# super.net
KiCad netlist of a schematic drawn in Altium Designer
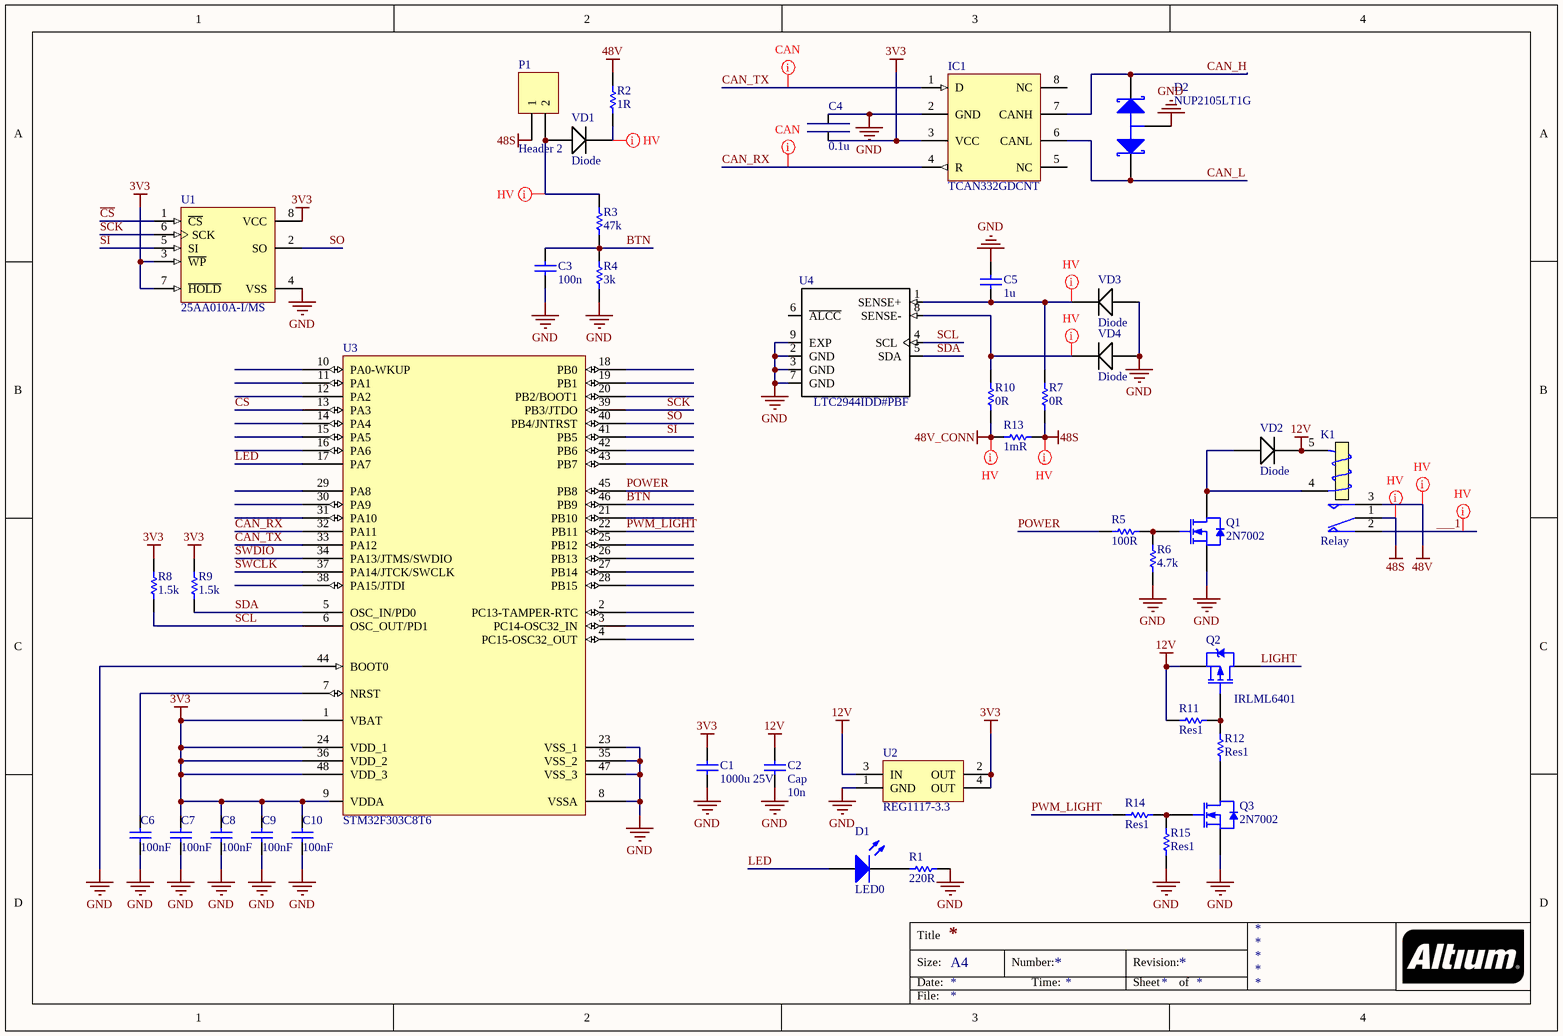
[diagram p0: super.SchDoc]

(export (version "E")
  (design (tool "Eeschema 10.0.6"))
  (components
    (comp (ref "C1")
      (value "1000u 25V")
      (footprint "RR_B")
      (description "Capacitor")
      (fields (field (name "PUBLISHER") "Altium Limited"))
      (libsource (lib "Miscellaneous Devices") (part "Cap"))
    )
    (comp (ref "C2")
      (value "Cap")
      (footprint "0603x")
      (description "Capacitor")
      (fields (field (name "ALTIUM_VALUE") "10n") (field (name "PUBLISHER") "Altium Limited"))
      (libsource (lib "Miscellaneous Devices") (part "Cap"))
    )
    (comp (ref "C3")
      (value "100n")
      (footprint "0603x")
      (description "Capacitor")
      (fields (field (name "PUBLISHER") "Altium Limited"))
      (libsource (lib "Miscellaneous Devices") (part "Cap"))
    )
    (comp (ref "C4")
      (value "0.1u")
      (footprint "Condensator:CAPC1608X08N(0603)")
      (libsource (lib "Condensator") (part "Ceramic Chip Capacitor"))
    )
    (comp (ref "C5")
      (value "1u")
      (footprint "0603x")
      (description "Capacitor")
      (fields (field (name "PUBLISHER") "Altium Limited"))
      (libsource (lib "Miscellaneous Devices") (part "Cap"))
    )
    (comp (ref "C6")
      (value "100nF")
      (footprint "0603x")
      (description "Capacitor")
      (fields (field (name "Comment") "Cap") (field (name "PUBLISHER") "Altium Limited"))
      (libsource (lib "Miscellaneous Devices") (part "Cap"))
    )
    (comp (ref "C7")
      (value "100nF")
      (footprint "0603x")
      (description "Capacitor")
      (fields (field (name "Comment") "Cap") (field (name "PUBLISHER") "Altium Limited"))
      (libsource (lib "Miscellaneous Devices") (part "Cap"))
    )
    (comp (ref "C8")
      (value "100nF")
      (footprint "0603x")
      (description "Capacitor")
      (fields (field (name "Comment") "Cap") (field (name "PUBLISHER") "Altium Limited"))
      (libsource (lib "Miscellaneous Devices") (part "Cap"))
    )
    (comp (ref "C9")
      (value "100nF")
      (footprint "0603x")
      (description "Capacitor")
      (fields (field (name "Comment") "Cap") (field (name "PUBLISHER") "Altium Limited"))
      (libsource (lib "Miscellaneous Devices") (part "Cap"))
    )
    (comp (ref "C10")
      (value "100nF")
      (footprint "0603x")
      (description "Capacitor")
      (fields (field (name "Comment") "Cap") (field (name "PUBLISHER") "Altium Limited"))
      (libsource (lib "Miscellaneous Devices") (part "Cap"))
    )
    (comp (ref "D1")
      (value "LED0")
      (footprint "HDR1X2")
      (description "Typical INFRARED GaAs LED")
      (fields (field (name "PUBLISHER") "Altium Limited"))
      (libsource (lib "Miscellaneous Devices") (part "LED0"))
    )
    (comp (ref "D2")
      (value "NUP2105LT1G")
      (footprint "SOT-23_M")
      (description "Schottky Barrier Double Diode")
      (libsource (lib "Philips Discrete Diode - Schottky") (part "BAT54A"))
    )
    (comp (ref "IC1")
      (value "TCAN332GDCNT")
      (footprint "SOT23-8_L")
      (libsource (lib "CustomLib") (part "TCAN332GDCNT"))
    )
    (comp (ref "K1")
      (value "Relay")
      (footprint "RELAY_12V_MICRO")
      (description "SPDT Relay")
      (fields (field (name "PUBLISHER") "Altium Limited"))
      (libsource (lib "Miscellaneous Devices") (part "Relay"))
    )
    (comp (ref "P1")
      (value "Header 2")
      (footprint "HDR1X2")
      (description "Header, 2-Pin")
      (fields (field (name "PUBLISHER") "Altium Limited"))
      (libsource (lib "Miscellaneous Connectors") (part "Header 2"))
    )
    (comp (ref "Q1")
      (value "2N7002")
      (footprint "SOT23_N")
      (description "N-channel Enhancement Mode Field-effect Transistor")
      (fields (field (name "PUBLISHER") "Altium Limited"))
      (libsource (lib "Philips Discrete MOSFET - Low Power") (part "2N7002"))
    )
    (comp (ref "Q2")
      (value "IRLML6401")
      (footprint "Micro3_N")
      (description "HEXFET Power MOSFET")
      (fields (field (name "PUBLISHER") "Altium Limited"))
      (libsource (lib "IR Discrete MOSFET - Power") (part "IRLML6401"))
    )
    (comp (ref "Q3")
      (value "2N7002")
      (footprint "SOT23_N")
      (description "N-channel Enhancement Mode Field-effect Transistor")
      (fields (field (name "PUBLISHER") "Altium Limited"))
      (libsource (lib "Philips Discrete MOSFET - Low Power") (part "2N7002"))
    )
    (comp (ref "R1")
      (value "220R")
      (footprint "0603x")
      (description "Resistor")
      (fields (field (name "PUBLISHER") "Altium Limited"))
      (libsource (lib "Miscellaneous Devices") (part "Res1"))
    )
    (comp (ref "R2")
      (value "1R")
      (footprint "2512")
      (description "Resistor")
      (fields (field (name "PUBLISHER") "Altium Limited"))
      (libsource (lib "Miscellaneous Devices") (part "Res1"))
    )
    (comp (ref "R3")
      (value "47k")
      (footprint "0603x")
      (description "Resistor")
      (fields (field (name "PUBLISHER") "Altium Limited"))
      (libsource (lib "Miscellaneous Devices") (part "Res1"))
    )
    (comp (ref "R4")
      (value "3k")
      (footprint "0603x")
      (description "Resistor")
      (fields (field (name "PUBLISHER") "Altium Limited"))
      (libsource (lib "Miscellaneous Devices") (part "Res1"))
    )
    (comp (ref "R5")
      (value "100R")
      (footprint "0603x")
      (description "Resistor")
      (fields (field (name "PUBLISHER") "Altium Limited"))
      (libsource (lib "Miscellaneous Devices") (part "Res1"))
    )
    (comp (ref "R6")
      (value "4.7k")
      (footprint "0603x")
      (description "Resistor")
      (fields (field (name "PUBLISHER") "Altium Limited"))
      (libsource (lib "Miscellaneous Devices") (part "Res1"))
    )
    (comp (ref "R7")
      (value "0R")
      (footprint "0603x")
      (description "Resistor")
      (fields (field (name "PUBLISHER") "Altium Limited"))
      (libsource (lib "Miscellaneous Devices") (part "Res1"))
    )
    (comp (ref "R8")
      (value "1.5k")
      (footprint "0603x")
      (description "Resistor")
      (fields (field (name "PUBLISHER") "Altium Limited"))
      (libsource (lib "Miscellaneous Devices") (part "Res1"))
    )
    (comp (ref "R9")
      (value "1.5k")
      (footprint "0603x")
      (description "Resistor")
      (fields (field (name "PUBLISHER") "Altium Limited"))
      (libsource (lib "Miscellaneous Devices") (part "Res1"))
    )
    (comp (ref "R10")
      (value "0R")
      (footprint "0603x")
      (description "Resistor")
      (fields (field (name "PUBLISHER") "Altium Limited"))
      (libsource (lib "Miscellaneous Devices") (part "Res1"))
    )
    (comp (ref "R11")
      (value "Res1")
      (footprint "0603x")
      (description "Resistor")
      (fields (field (name "PUBLISHER") "Altium Limited"))
      (libsource (lib "Miscellaneous Devices") (part "Res1"))
    )
    (comp (ref "R12")
      (value "Res1")
      (footprint "0603x")
      (description "Resistor")
      (fields (field (name "PUBLISHER") "Altium Limited"))
      (libsource (lib "Miscellaneous Devices") (part "Res1"))
    )
    (comp (ref "R13")
      (value "1mR")
      (footprint "2512")
      (description "Resistor")
      (fields (field (name "PUBLISHER") "Altium Limited"))
      (libsource (lib "Miscellaneous Devices") (part "Res1"))
    )
    (comp (ref "R14")
      (value "Res1")
      (footprint "0603x")
      (description "Resistor")
      (fields (field (name "PUBLISHER") "Altium Limited"))
      (libsource (lib "Miscellaneous Devices") (part "Res1"))
    )
    (comp (ref "R15")
      (value "Res1")
      (footprint "0603x")
      (description "Resistor")
      (fields (field (name "PUBLISHER") "Altium Limited"))
      (libsource (lib "Miscellaneous Devices") (part "Res1"))
    )
    (comp (ref "U1")
      (value "25AA010A-I/MS")
      (footprint "SO-8_N")
      (description "1K SPI Bus Serial EEPROM, 8-Pin MSOP, Industrial Temperature")
      (fields (field (name "PUBLISHER") "Altium Limited"))
      (libsource (lib "Microchip Memory SPI Serial EEPROM") (part "25AA010A-I/MS"))
    )
    (comp (ref "U2")
      (value "REG1117-3.3")
      (footprint "SOt-223_L")
      (description "800mA and 1A Low Dropout Positive Regulator 2.85V, 3.3V, 5V, and Adjustable")
      (fields (field (name "PUBLISHER") "Altium Limited"))
      (libsource (lib "BB Power Mgt Voltage Regulator") (part "REG1117-3.3"))
    )
    (comp (ref "U3")
      (value "STM32F303C8T6")
      (footprint "LQFP48_N")
      (description "STM32 ARM-based 32-bit MCU with 32 Kbytes Flash, 48-pin LQFP, Industrial Temperature")
      (fields (field (name "PUBLISHER") "Altium Limited"))
      (libsource (lib "ST Microcontroller 32-Bit STM32") (part "STM32F103C6T6"))
    )
    (comp (ref "U4")
      (value "LTC2944IDD#PBF")
      (footprint "SON300X300X80-9N")
      (description "LTC2944 - 60V Battery Gas Gauge with Temperature, Voltage and Current Measurement")
      (fields (field (name "MF") "Linear Technology"))
      (libsource (lib "LTC2944IDD_PBF") (part "LTC2944IDD#PBF"))
    )
    (comp (ref "VD1")
      (value "Diode")
      (footprint "SOD-80/MLL34")
      (description "Default Diode")
      (fields (field (name "PUBLISHER") "Altium Limited"))
      (libsource (lib "EDDLib") (part "Diode"))
    )
    (comp (ref "VD2")
      (value "Diode")
      (footprint "SOD-80/MLL34")
      (description "Default Diode")
      (fields (field (name "PUBLISHER") "Altium Limited"))
      (libsource (lib "EDDLib") (part "Diode"))
    )
    (comp (ref "VD3")
      (value "Diode")
      (footprint "SMB_real")
      (description "Default Diode")
      (fields (field (name "PUBLISHER") "Altium Limited"))
      (libsource (lib "EDDLib") (part "Diode"))
    )
    (comp (ref "VD4")
      (value "Diode")
      (footprint "SMB_real")
      (description "Default Diode")
      (fields (field (name "PUBLISHER") "Altium Limited"))
      (libsource (lib "EDDLib") (part "Diode"))
    )
  )
  (nets
    (net (code "1") (name "/BTN") (class "Default")
      (node (ref "C3") (pin "1") (pinfunction "1_1") (pintype "passive"))
      (node (ref "R3") (pin "1") (pinfunction "1_1") (pintype "passive"))
      (node (ref "R4") (pin "2") (pinfunction "2_2") (pintype "passive"))
      (node (ref "U3") (pin "46") (pinfunction "PB9_46") (pintype "bidirectional"))
    )
    (net (code "2") (name "/CAN_H") (class "Default")
      (node (ref "D2") (pin "1") (pinfunction "K1_1") (pintype "passive"))
      (node (ref "IC1") (pin "7") (pinfunction "CANH_7") (pintype "passive"))
    )
    (net (code "3") (name "/CAN_L") (class "Default")
      (node (ref "D2") (pin "2") (pinfunction "K2_2") (pintype "passive"))
      (node (ref "IC1") (pin "6") (pinfunction "CANL_6") (pintype "passive"))
    )
    (net (code "4") (name "/CAN_RX") (class "Default")
      (node (ref "IC1") (pin "4") (pinfunction "R_4") (pintype "output"))
      (node (ref "U3") (pin "32") (pinfunction "PA11_32") (pintype "passive"))
    )
    (net (code "5") (name "/CAN_TX") (class "Default")
      (node (ref "IC1") (pin "1") (pinfunction "D_1") (pintype "input"))
      (node (ref "U3") (pin "33") (pinfunction "PA12_33") (pintype "passive"))
    )
    (net (code "6") (name "/LED") (class "Default")
      (node (ref "D1") (pin "1") (pinfunction "A_1") (pintype "passive"))
      (node (ref "U3") (pin "17") (pinfunction "PA7_17") (pintype "passive"))
    )
    (net (code "7") (name "/LIGHT") (class "Default")
      (node (ref "Q2") (pin "3") (pinfunction "D_3") (pintype "passive"))
    )
    (net (code "8") (name "/POWER") (class "Default")
      (node (ref "R5") (pin "1") (pinfunction "1_1") (pintype "passive"))
      (node (ref "U3") (pin "45") (pinfunction "PB8_45") (pintype "bidirectional"))
    )
    (net (code "9") (name "/PWM_LIGHT") (class "Default")
      (node (ref "R14") (pin "1") (pinfunction "1_1") (pintype "passive"))
      (node (ref "U3") (pin "22") (pinfunction "PB11_22") (pintype "bidirectional"))
    )
    (net (code "10") (name "/SCK") (class "Default")
      (node (ref "U1") (pin "6") (pinfunction "SCK_6") (pintype "input"))
      (node (ref "U3") (pin "39") (pinfunction "PB3/JTDO_39") (pintype "bidirectional"))
    )
    (net (code "11") (name "/SCL") (class "Default")
      (node (ref "R8") (pin "1") (pinfunction "1_1") (pintype "passive"))
      (node (ref "U3") (pin "6") (pinfunction "OSC_OUT/PD1_6") (pintype "passive"))
      (node (ref "U4") (pin "4") (pinfunction "SCL_4") (pintype "input"))
    )
    (net (code "12") (name "/SDA") (class "Default")
      (node (ref "R9") (pin "1") (pinfunction "1_1") (pintype "passive"))
      (node (ref "U3") (pin "5") (pinfunction "OSC_IN/PD0_5") (pintype "passive"))
      (node (ref "U4") (pin "5") (pinfunction "SDA_5") (pintype "bidirectional"))
    )
    (net (code "13") (name "/SI") (class "Default")
      (node (ref "U1") (pin "5") (pinfunction "SI_5") (pintype "input"))
      (node (ref "U3") (pin "41") (pinfunction "PB5_41") (pintype "bidirectional"))
    )
    (net (code "14") (name "/SO") (class "Default")
      (node (ref "U1") (pin "2") (pinfunction "SO_2") (pintype "tri_state"))
      (node (ref "U3") (pin "40") (pinfunction "PB4/JNTRST_40") (pintype "bidirectional"))
    )
    (net (code "15") (name "/SWCLK") (class "Default")
      (node (ref "U3") (pin "37") (pinfunction "PA14/JTCK/SWCLK_37") (pintype "passive"))
    )
    (net (code "16") (name "/SWDIO") (class "Default")
      (node (ref "U3") (pin "34") (pinfunction "PA13/JTMS/SWDIO_34") (pintype "passive"))
    )
    (net (code "17") (name "/___1") (class "Default")
      (node (ref "K1") (pin "2") (pinfunction "NC_2") (pintype "passive"))
    )
    (net (code "18") (name "/~{CS}") (class "Default")
      (node (ref "U1") (pin "1") (pinfunction "~{CS}_1") (pintype "input"))
      (node (ref "U3") (pin "13") (pinfunction "PA3_13") (pintype "bidirectional"))
    )
    (net (code "19") (name "3V3") (class "Default")
      (node (ref "C1") (pin "1") (pinfunction "1_1") (pintype "passive"))
      (node (ref "C10") (pin "2") (pinfunction "2_2") (pintype "passive"))
      (node (ref "C4") (pin "2") (pintype "passive"))
      (node (ref "C7") (pin "2") (pinfunction "2_2") (pintype "passive"))
      (node (ref "C8") (pin "2") (pinfunction "2_2") (pintype "passive"))
      (node (ref "C9") (pin "2") (pinfunction "2_2") (pintype "passive"))
      (node (ref "IC1") (pin "3") (pinfunction "VCC_3") (pintype "passive"))
      (node (ref "R8") (pin "2") (pinfunction "2_2") (pintype "passive"))
      (node (ref "R9") (pin "2") (pinfunction "2_2") (pintype "passive"))
      (node (ref "U1") (pin "3") (pinfunction "~{WP}_3") (pintype "input"))
      (node (ref "U1") (pin "7") (pinfunction "~{HOLD}_7") (pintype "input"))
      (node (ref "U1") (pin "8") (pinfunction "VCC_8") (pintype "power_in"))
      (node (ref "U2") (pin "2") (pinfunction "OUT_2") (pintype "power_in"))
      (node (ref "U2") (pin "4") (pinfunction "OUT_4") (pintype "power_in"))
      (node (ref "U3") (pin "1") (pinfunction "VBAT_1") (pintype "power_in"))
      (node (ref "U3") (pin "24") (pinfunction "VDD_1_24") (pintype "power_in"))
      (node (ref "U3") (pin "36") (pinfunction "VDD_2_36") (pintype "power_in"))
      (node (ref "U3") (pin "48") (pinfunction "VDD_3_48") (pintype "power_in"))
      (node (ref "U3") (pin "9") (pinfunction "VDDA_9") (pintype "power_in"))
    )
    (net (code "20") (name "12V") (class "Default")
      (node (ref "C2") (pin "1") (pinfunction "1_1") (pintype "passive"))
      (node (ref "K1") (pin "5") (pinfunction "T2_5") (pintype "passive"))
      (node (ref "Q2") (pin "2") (pinfunction "S_2") (pintype "passive"))
      (node (ref "R11") (pin "1") (pinfunction "1_1") (pintype "passive"))
      (node (ref "U2") (pin "3") (pinfunction "IN_3") (pintype "power_in"))
      (node (ref "VD2") (pin "2") (pinfunction "K_2") (pintype "passive"))
    )
    (net (code "21") (name "48S") (class "Default")
      (node (ref "K1") (pin "1") (pinfunction "COM_1") (pintype "passive"))
      (node (ref "P1") (pin "1") (pinfunction "1_1") (pintype "passive"))
      (node (ref "R13") (pin "2") (pinfunction "2_2") (pintype "passive"))
      (node (ref "R7") (pin "2") (pinfunction "2_2") (pintype "passive"))
    )
    (net (code "22") (name "48V") (class "Default")
      (node (ref "K1") (pin "3") (pinfunction "NO_3") (pintype "passive"))
      (node (ref "R2") (pin "2") (pinfunction "2_2") (pintype "passive"))
    )
    (net (code "23") (name "48V_CONN") (class "Default")
      (node (ref "R10") (pin "2") (pinfunction "2_2") (pintype "passive"))
      (node (ref "R13") (pin "1") (pinfunction "1_1") (pintype "passive"))
    )
    (net (code "24") (name "GND") (class "Default")
      (node (ref "C1") (pin "2") (pinfunction "2_2") (pintype "passive"))
      (node (ref "C10") (pin "1") (pinfunction "1_1") (pintype "passive"))
      (node (ref "C2") (pin "2") (pinfunction "2_2") (pintype "passive"))
      (node (ref "C3") (pin "2") (pinfunction "2_2") (pintype "passive"))
      (node (ref "C4") (pin "1") (pintype "passive"))
      (node (ref "C5") (pin "2") (pinfunction "2_2") (pintype "passive"))
      (node (ref "C6") (pin "1") (pinfunction "1_1") (pintype "passive"))
      (node (ref "C7") (pin "1") (pinfunction "1_1") (pintype "passive"))
      (node (ref "C8") (pin "1") (pinfunction "1_1") (pintype "passive"))
      (node (ref "C9") (pin "1") (pinfunction "1_1") (pintype "passive"))
      (node (ref "D2") (pin "3") (pinfunction "A_3") (pintype "passive"))
      (node (ref "IC1") (pin "2") (pinfunction "GND_2") (pintype "power_in"))
      (node (ref "Q1") (pin "2") (pinfunction "S_2") (pintype "passive"))
      (node (ref "Q3") (pin "2") (pinfunction "S_2") (pintype "passive"))
      (node (ref "R1") (pin "2") (pinfunction "2_2") (pintype "passive"))
      (node (ref "R15") (pin "1") (pinfunction "1_1") (pintype "passive"))
      (node (ref "R4") (pin "1") (pinfunction "1_1") (pintype "passive"))
      (node (ref "R6") (pin "1") (pinfunction "1_1") (pintype "passive"))
      (node (ref "U1") (pin "4") (pinfunction "VSS_4") (pintype "power_in"))
      (node (ref "U2") (pin "1") (pinfunction "GND_1") (pintype "power_in"))
      (node (ref "U3") (pin "23") (pinfunction "VSS_1_23") (pintype "power_in"))
      (node (ref "U3") (pin "35") (pinfunction "VSS_2_35") (pintype "power_in"))
      (node (ref "U3") (pin "44") (pinfunction "BOOT0_44") (pintype "input"))
      (node (ref "U3") (pin "47") (pinfunction "VSS_3_47") (pintype "power_in"))
      (node (ref "U3") (pin "8") (pinfunction "VSSA_8") (pintype "power_in"))
      (node (ref "U4") (pin "2") (pinfunction "GND_2") (pintype "power_in"))
      (node (ref "U4") (pin "3") (pinfunction "GND_3") (pintype "power_in"))
      (node (ref "U4") (pin "7") (pinfunction "GND_7") (pintype "power_in"))
      (node (ref "U4") (pin "9") (pinfunction "EXP_9") (pintype "passive"))
      (node (ref "VD3") (pin "1") (pinfunction "A_1") (pintype "passive"))
      (node (ref "VD4") (pin "1") (pinfunction "A_1") (pintype "passive"))
    )
    (net (code "25") (name "Net-(D1-K)") (class "Default")
      (node (ref "D1") (pin "2") (pinfunction "K_2") (pintype "passive"))
      (node (ref "R1") (pin "1") (pinfunction "1_1") (pintype "passive"))
    )
    (net (code "26") (name "Net-(K1-T1)") (class "Default")
      (node (ref "K1") (pin "4") (pinfunction "T1_4") (pintype "passive"))
      (node (ref "Q1") (pin "3") (pinfunction "D_3") (pintype "passive"))
      (node (ref "VD2") (pin "1") (pinfunction "A_1") (pintype "passive"))
    )
    (net (code "27") (name "Net-(Q1-G)") (class "Default")
      (node (ref "Q1") (pin "1") (pinfunction "G_1") (pintype "passive"))
      (node (ref "R5") (pin "2") (pinfunction "2_2") (pintype "passive"))
      (node (ref "R6") (pin "2") (pinfunction "2_2") (pintype "passive"))
    )
    (net (code "28") (name "Net-(Q2-G)") (class "Default")
      (node (ref "Q2") (pin "1") (pinfunction "G_1") (pintype "passive"))
      (node (ref "R11") (pin "2") (pinfunction "2_2") (pintype "passive"))
      (node (ref "R12") (pin "1") (pinfunction "1_1") (pintype "passive"))
    )
    (net (code "29") (name "Net-(Q3-D)") (class "Default")
      (node (ref "Q3") (pin "3") (pinfunction "D_3") (pintype "passive"))
      (node (ref "R12") (pin "2") (pinfunction "2_2") (pintype "passive"))
    )
    (net (code "30") (name "Net-(Q3-G)") (class "Default")
      (node (ref "Q3") (pin "1") (pinfunction "G_1") (pintype "passive"))
      (node (ref "R14") (pin "2") (pinfunction "2_2") (pintype "passive"))
      (node (ref "R15") (pin "2") (pinfunction "2_2") (pintype "passive"))
    )
    (net (code "31") (name "Net-(U3-NRST)") (class "Default")
      (node (ref "C6") (pin "2") (pinfunction "2_2") (pintype "passive"))
      (node (ref "U3") (pin "7") (pinfunction "NRST_7") (pintype "bidirectional"))
    )
    (net (code "32") (name "Net-(U4-SENSE+)") (class "Default")
      (node (ref "C5") (pin "1") (pinfunction "1_1") (pintype "passive"))
      (node (ref "R7") (pin "1") (pinfunction "1_1") (pintype "passive"))
      (node (ref "U4") (pin "1") (pinfunction "SENSE+_1") (pintype "input"))
      (node (ref "VD3") (pin "2") (pinfunction "K_2") (pintype "passive"))
    )
    (net (code "33") (name "Net-(U4-SENSE-)") (class "Default")
      (node (ref "R10") (pin "1") (pinfunction "1_1") (pintype "passive"))
      (node (ref "U4") (pin "8") (pinfunction "SENSE-_8") (pintype "input"))
      (node (ref "VD4") (pin "2") (pinfunction "K_2") (pintype "passive"))
    )
    (net (code "34") (name "Net-(VD1-A)") (class "Default")
      (node (ref "P1") (pin "2") (pinfunction "2_2") (pintype "passive"))
      (node (ref "R3") (pin "2") (pinfunction "2_2") (pintype "passive"))
      (node (ref "VD1") (pin "1") (pinfunction "A_1") (pintype "passive"))
    )
    (net (code "35") (name "Net-(VD1-K)") (class "Default")
      (node (ref "R2") (pin "1") (pinfunction "1_1") (pintype "passive"))
      (node (ref "VD1") (pin "2") (pinfunction "K_2") (pintype "passive"))
    )
    (net (code "36") (name "unconnected-(IC1-NC-Pad5)") (class "Default")
      (node (ref "IC1") (pin "5") (pinfunction "NC_5") (pintype "passive"))
    )
    (net (code "37") (name "unconnected-(IC1-NC-Pad8)") (class "Default")
      (node (ref "IC1") (pin "8") (pinfunction "NC_8") (pintype "passive"))
    )
    (net (code "38") (name "unconnected-(U3-PA0-WKUP-Pad10)") (class "Default")
      (node (ref "U3") (pin "10") (pinfunction "PA0-WKUP_10") (pintype "bidirectional"))
    )
    (net (code "39") (name "unconnected-(U3-PA1-Pad11)") (class "Default")
      (node (ref "U3") (pin "11") (pinfunction "PA1_11") (pintype "bidirectional"))
    )
    (net (code "40") (name "unconnected-(U3-PA2-Pad12)") (class "Default")
      (node (ref "U3") (pin "12") (pinfunction "PA2_12") (pintype "passive"))
    )
    (net (code "41") (name "unconnected-(U3-PA4-Pad14)") (class "Default")
      (node (ref "U3") (pin "14") (pinfunction "PA4_14") (pintype "bidirectional"))
    )
    (net (code "42") (name "unconnected-(U3-PA5-Pad15)") (class "Default")
      (node (ref "U3") (pin "15") (pinfunction "PA5_15") (pintype "bidirectional"))
    )
    (net (code "43") (name "unconnected-(U3-PA6-Pad16)") (class "Default")
      (node (ref "U3") (pin "16") (pinfunction "PA6_16") (pintype "bidirectional"))
    )
    (net (code "44") (name "unconnected-(U3-PA8-Pad29)") (class "Default")
      (node (ref "U3") (pin "29") (pinfunction "PA8_29") (pintype "passive"))
    )
    (net (code "45") (name "unconnected-(U3-PA9-Pad30)") (class "Default")
      (node (ref "U3") (pin "30") (pinfunction "PA9_30") (pintype "bidirectional"))
    )
    (net (code "46") (name "unconnected-(U3-PA10-Pad31)") (class "Default")
      (node (ref "U3") (pin "31") (pinfunction "PA10_31") (pintype "bidirectional"))
    )
    (net (code "47") (name "unconnected-(U3-PA15{slash}JTDI-Pad38)") (class "Default")
      (node (ref "U3") (pin "38") (pinfunction "PA15/JTDI_38") (pintype "bidirectional"))
    )
    (net (code "48") (name "unconnected-(U3-PB0-Pad18)") (class "Default")
      (node (ref "U3") (pin "18") (pinfunction "PB0_18") (pintype "bidirectional"))
    )
    (net (code "49") (name "unconnected-(U3-PB1-Pad19)") (class "Default")
      (node (ref "U3") (pin "19") (pinfunction "PB1_19") (pintype "bidirectional"))
    )
    (net (code "50") (name "unconnected-(U3-PB2{slash}BOOT1-Pad20)") (class "Default")
      (node (ref "U3") (pin "20") (pinfunction "PB2/BOOT1_20") (pintype "bidirectional"))
    )
    (net (code "51") (name "unconnected-(U3-PB6-Pad42)") (class "Default")
      (node (ref "U3") (pin "42") (pinfunction "PB6_42") (pintype "bidirectional"))
    )
    (net (code "52") (name "unconnected-(U3-PB7-Pad43)") (class "Default")
      (node (ref "U3") (pin "43") (pinfunction "PB7_43") (pintype "bidirectional"))
    )
    (net (code "53") (name "unconnected-(U3-PB10-Pad21)") (class "Default")
      (node (ref "U3") (pin "21") (pinfunction "PB10_21") (pintype "bidirectional"))
    )
    (net (code "54") (name "unconnected-(U3-PB12-Pad25)") (class "Default")
      (node (ref "U3") (pin "25") (pinfunction "PB12_25") (pintype "bidirectional"))
    )
    (net (code "55") (name "unconnected-(U3-PB13-Pad26)") (class "Default")
      (node (ref "U3") (pin "26") (pinfunction "PB13_26") (pintype "bidirectional"))
    )
    (net (code "56") (name "unconnected-(U3-PB14-Pad27)") (class "Default")
      (node (ref "U3") (pin "27") (pinfunction "PB14_27") (pintype "bidirectional"))
    )
    (net (code "57") (name "unconnected-(U3-PB15-Pad28)") (class "Default")
      (node (ref "U3") (pin "28") (pinfunction "PB15_28") (pintype "bidirectional"))
    )
    (net (code "58") (name "unconnected-(U3-PC13-TAMPER-RTC-Pad2)") (class "Default")
      (node (ref "U3") (pin "2") (pinfunction "PC13-TAMPER-RTC_2") (pintype "bidirectional"))
    )
    (net (code "59") (name "unconnected-(U3-PC14-OSC32_IN-Pad3)") (class "Default")
      (node (ref "U3") (pin "3") (pinfunction "PC14-OSC32_IN_3") (pintype "bidirectional"))
    )
    (net (code "60") (name "unconnected-(U3-PC15-OSC32_OUT-Pad4)") (class "Default")
      (node (ref "U3") (pin "4") (pinfunction "PC15-OSC32_OUT_4") (pintype "bidirectional"))
    )
    (net (code "61") (name "unconnected-(U4-~{ALCC}-Pad6)") (class "Default")
      (node (ref "U4") (pin "6") (pinfunction "~{ALCC}_6") (pintype "bidirectional"))
    )
  )
)
